# S7CAS-PLEIADES-CARTE-MERE_P01_MOTORS.net
KiCad netlist of a schematic drawn in Altium Designer
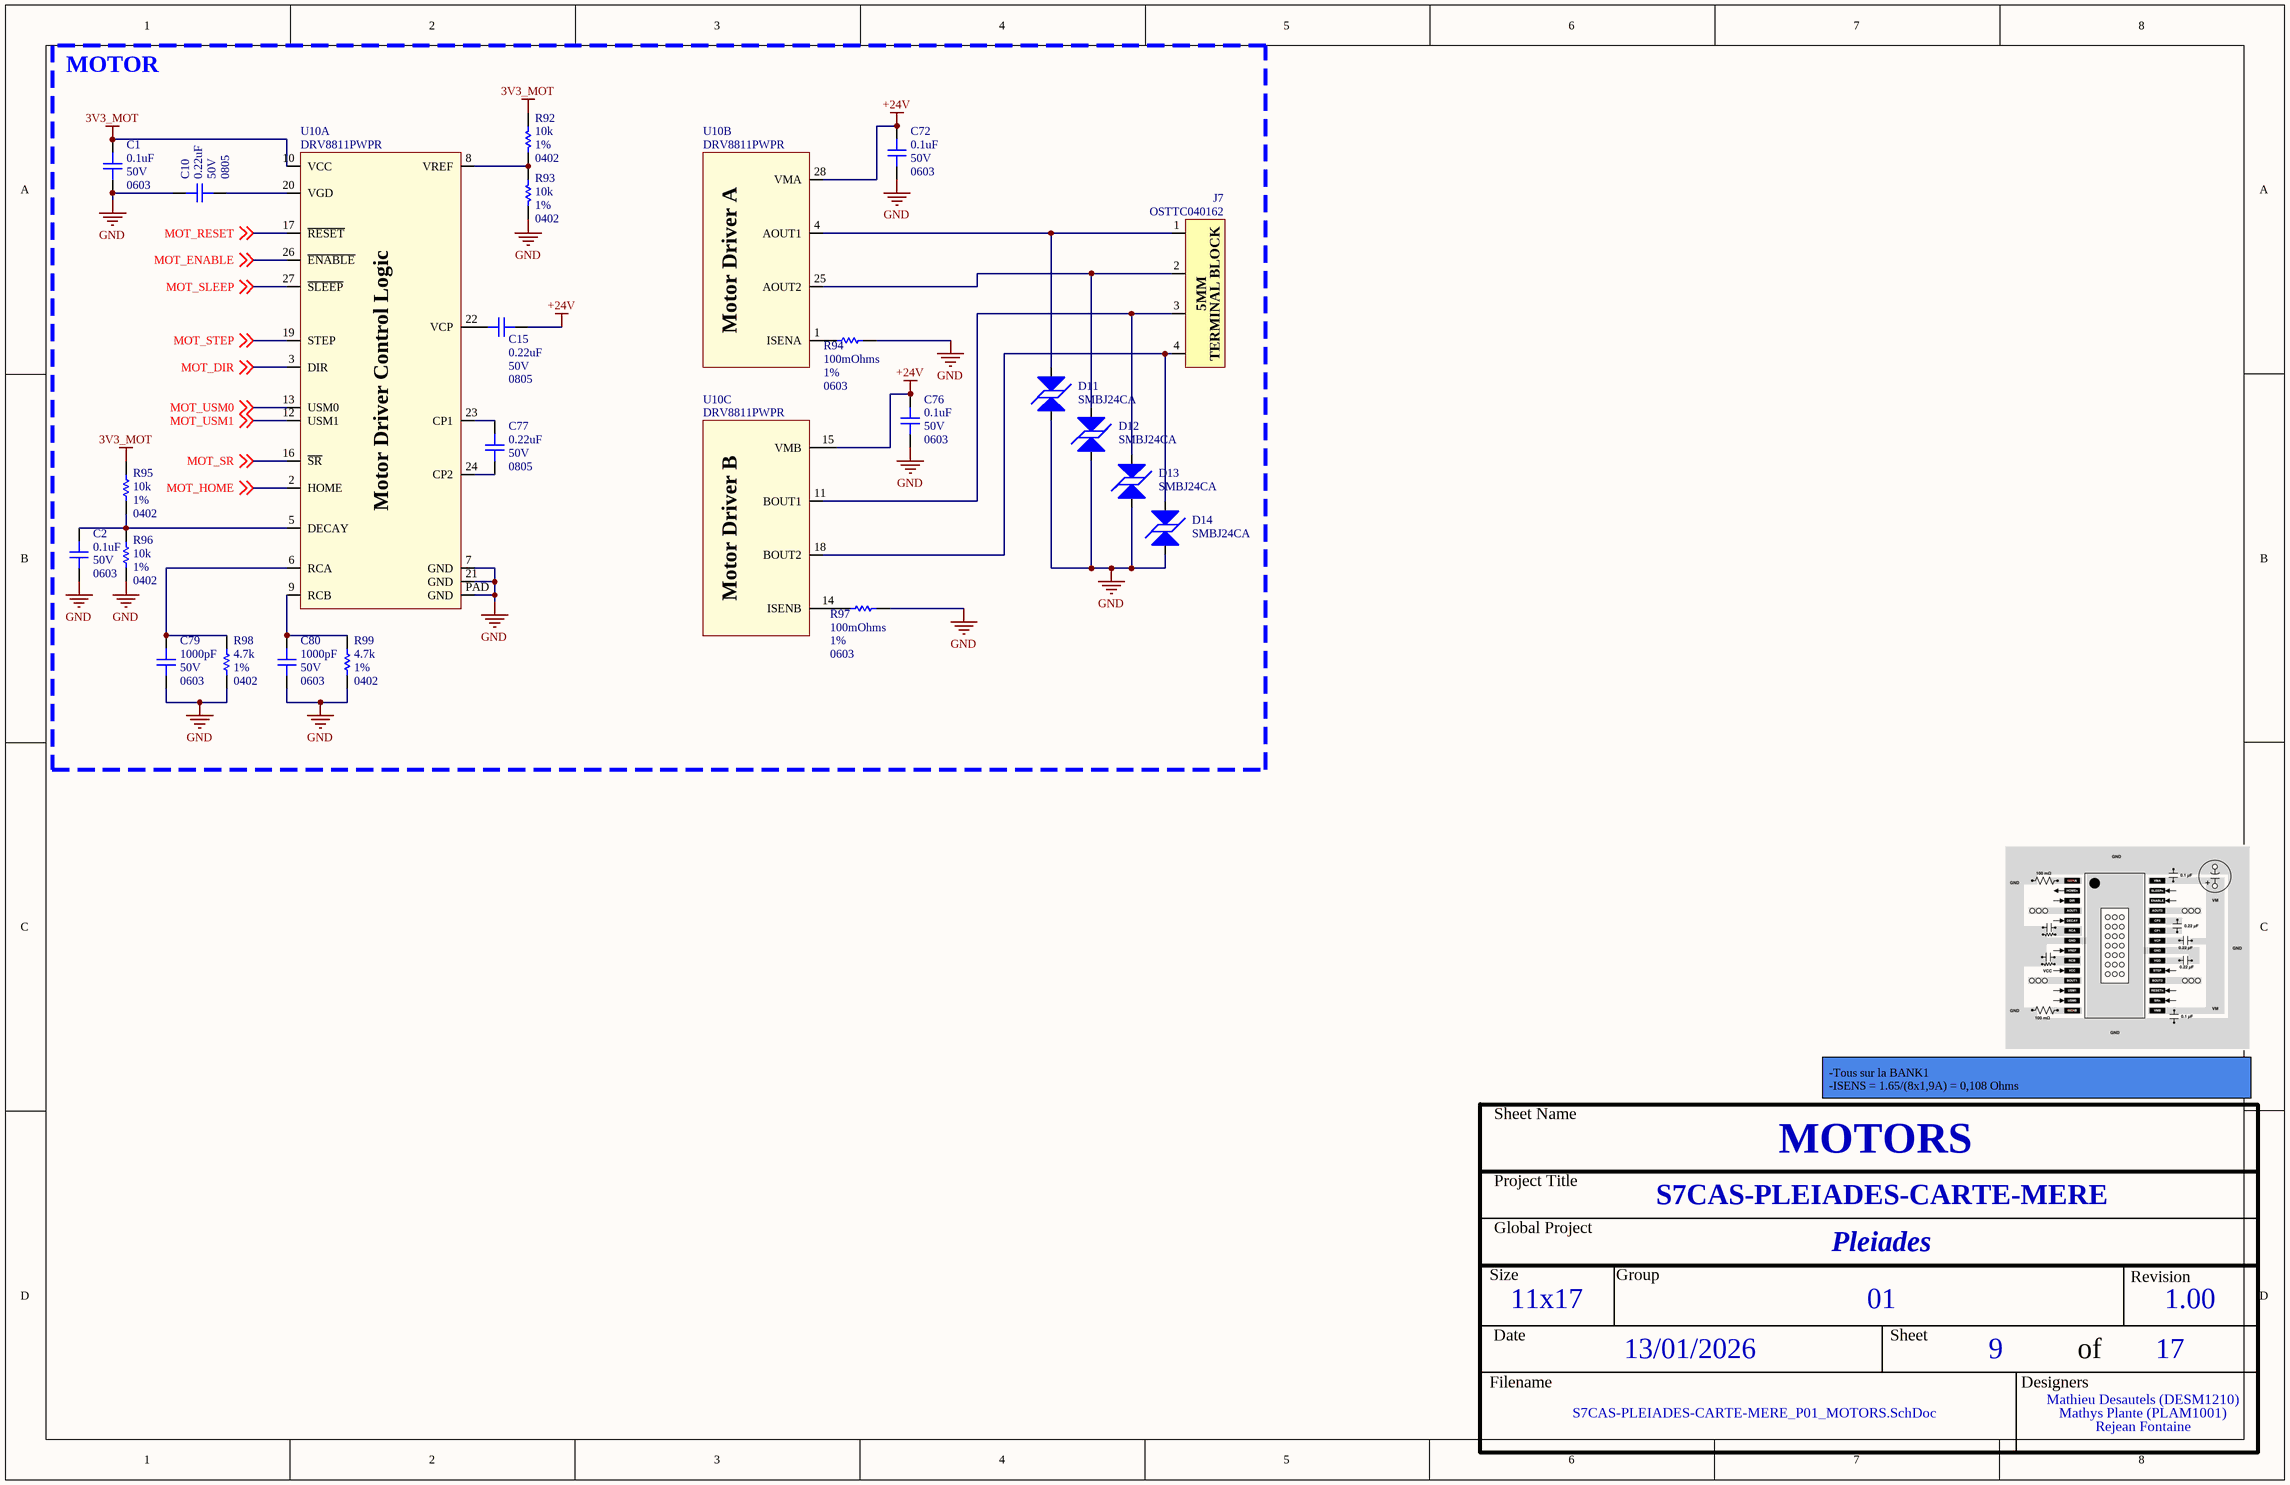
[diagram p0: S7CAS-PLEIADES-CARTE-MERE_P01_MOTORS.SchDoc]

(export (version "E")
  (design (tool "Eeschema 10.0.6"))
  (components
    (comp (ref "C1")
      (value "0.1uF")
      (footprint "CAP_0603")
      (description "0.1 µF ±10% 50V Ceramic Capacitor X7R 0603 (1608 Metric)")
      (fields
        (field (name "MFG") "KEMET")
        (field (name "MFG PART NUMBER") "C0603C104K5RACTU")
        (field (name "VOLTAGE") "50V")
        (field (name "PACKAGE") "0603")
        (field (name "CREATEDBY") "Jonathan Bouchard")
      )
      (libsource (lib "s7cas_lib2023") (part "CAP - 0603"))
    )
    (comp (ref "C2")
      (value "0.1uF")
      (footprint "CAP_0603")
      (description "0.1 µF ±10% 50V Ceramic Capacitor X7R 0603 (1608 Metric)")
      (fields
        (field (name "MFG") "KEMET")
        (field (name "MFG PART NUMBER") "C0603C104K5RACTU")
        (field (name "VOLTAGE") "50V")
        (field (name "PACKAGE") "0603")
        (field (name "CREATEDBY") "Jonathan Bouchard")
      )
      (libsource (lib "s7cas_lib2023") (part "CAP - 0603"))
    )
    (comp (ref "C10")
      (value "0.22uF")
      (footprint "CAP_0805")
      (description "0.22 µF ±10% 50V Ceramic Capacitor X7R 0805 (2012 Metric)")
      (fields
        (field (name "MFG PART NUMBER") "C0805C224K5RACTU")
        (field (name "VOLTAGE") "50V")
        (field (name "PACKAGE") "0805")
        (field (name "Comment") "CAP - 0805")
        (field (name "CREATEDBY") "Jonathan Bouchard")
      )
      (libsource (lib "s7cas_lib2023") (part "CAP - 0805"))
    )
    (comp (ref "C15")
      (value "0.22uF")
      (footprint "CAP_0805")
      (description "0.22 µF ±10% 50V Ceramic Capacitor X7R 0805 (2012 Metric)")
      (fields
        (field (name "MFG PART NUMBER") "C0805C224K5RACTU")
        (field (name "VOLTAGE") "50V")
        (field (name "PACKAGE") "0805")
        (field (name "Comment") "CAP - 0805")
        (field (name "CREATEDBY") "Jonathan Bouchard")
      )
      (libsource (lib "s7cas_lib2023") (part "CAP - 0805"))
    )
    (comp (ref "C72")
      (value "0.1uF")
      (footprint "CAP_0603")
      (description "0.1 µF ±10% 50V Ceramic Capacitor X7R 0603 (1608 Metric)")
      (fields
        (field (name "MFG") "KEMET")
        (field (name "MFG PART NUMBER") "C0603C104K5RACTU")
        (field (name "VOLTAGE") "50V")
        (field (name "PACKAGE") "0603")
        (field (name "CREATEDBY") "Jonathan Bouchard")
      )
      (libsource (lib "s7cas_lib2023") (part "CAP - 0603"))
    )
    (comp (ref "C76")
      (value "0.1uF")
      (footprint "CAP_0603")
      (description "0.1 µF ±10% 50V Ceramic Capacitor X7R 0603 (1608 Metric)")
      (fields
        (field (name "MFG") "KEMET")
        (field (name "MFG PART NUMBER") "C0603C104K5RACTU")
        (field (name "VOLTAGE") "50V")
        (field (name "PACKAGE") "0603")
        (field (name "CREATEDBY") "Jonathan Bouchard")
      )
      (libsource (lib "s7cas_lib2023") (part "CAP - 0603"))
    )
    (comp (ref "C77")
      (value "0.22uF")
      (footprint "CAP_0805")
      (description "0.22 µF ±10% 50V Ceramic Capacitor X7R 0805 (2012 Metric)")
      (fields
        (field (name "MFG PART NUMBER") "C0805C224K5RACTU")
        (field (name "VOLTAGE") "50V")
        (field (name "PACKAGE") "0805")
        (field (name "Comment") "CAP - 0805")
        (field (name "CREATEDBY") "Jonathan Bouchard")
      )
      (libsource (lib "s7cas_lib2023") (part "CAP - 0805"))
    )
    (comp (ref "C79")
      (value "1000pF")
      (footprint "CAP_0603")
      (description "1000 pF ±10% 50V Ceramic Capacitor X7R 0603 (1608 Metric)")
      (fields
        (field (name "MFG") "KEMET")
        (field (name "MFG PART NUMBER") "C0603C102K5RACTU")
        (field (name "VOLTAGE") "50V")
        (field (name "PACKAGE") "0603")
        (field (name "CREATEDBY") "Jonathan Bouchard")
      )
      (libsource (lib "s7cas_lib2023") (part "CAP - 0603"))
    )
    (comp (ref "C80")
      (value "1000pF")
      (footprint "CAP_0603")
      (description "1000 pF ±10% 50V Ceramic Capacitor X7R 0603 (1608 Metric)")
      (fields
        (field (name "MFG") "KEMET")
        (field (name "MFG PART NUMBER") "C0603C102K5RACTU")
        (field (name "VOLTAGE") "50V")
        (field (name "PACKAGE") "0603")
        (field (name "CREATEDBY") "Jonathan Bouchard")
      )
      (libsource (lib "s7cas_lib2023") (part "CAP - 0603"))
    )
    (comp (ref "D11")
      (value "SMBJ24CA")
      (footprint "TVS_PWR_SMBJ36CA")
      (description "TVS - 24V 26.7V 600W - DO214AA")
      (fields
        (field (name "CREATEDBY/DATE") "Arnaud Samson - 06/07/18")
        (field (name "VERIFIEDBY") "Jonathan Bouchard - 2018-07-13")
      )
      (libsource (lib "s7cas_lib2023") (part "TVS_PWR_SMBJ24CA"))
    )
    (comp (ref "D12")
      (value "SMBJ24CA")
      (footprint "TVS_PWR_SMBJ36CA")
      (description "TVS - 24V 26.7V 600W - DO214AA")
      (fields
        (field (name "CREATEDBY/DATE") "Arnaud Samson - 06/07/18")
        (field (name "VERIFIEDBY") "Jonathan Bouchard - 2018-07-13")
      )
      (libsource (lib "s7cas_lib2023") (part "TVS_PWR_SMBJ24CA"))
    )
    (comp (ref "D13")
      (value "SMBJ24CA")
      (footprint "TVS_PWR_SMBJ36CA")
      (description "TVS - 24V 26.7V 600W - DO214AA")
      (fields
        (field (name "CREATEDBY/DATE") "Arnaud Samson - 06/07/18")
        (field (name "VERIFIEDBY") "Jonathan Bouchard - 2018-07-13")
      )
      (libsource (lib "s7cas_lib2023") (part "TVS_PWR_SMBJ24CA"))
    )
    (comp (ref "D14")
      (value "SMBJ24CA")
      (footprint "TVS_PWR_SMBJ36CA")
      (description "TVS - 24V 26.7V 600W - DO214AA")
      (fields
        (field (name "CREATEDBY/DATE") "Arnaud Samson - 06/07/18")
        (field (name "VERIFIEDBY") "Jonathan Bouchard - 2018-07-13")
      )
      (libsource (lib "s7cas_lib2023") (part "TVS_PWR_SMBJ24CA"))
    )
    (comp (ref "J7")
      (value "OSTTC040162")
      (footprint "CONN_TERMINAL_OSTTA040161")
      (description "CONN -  TERMINAL BLOCK 4POS 5MM - TH")
      (fields (field (name "MFG") "On Shore Technology Inc.") (field (name "CREATEDBY") "Jonathan Bouchard"))
      (libsource (lib "s7cas_lib2023") (part "CONN_TERMINAL_OSTTC040162"))
    )
    (comp (ref "R92")
      (value "10k")
      (footprint "RES_0402")
      (description "10 kOhms ±1% 0.063W, 1/16W Chip Resistor 0402 (1005 Metric) Automotive AEC-Q200 Thick Film")
      (fields
        (field (name "VOLTAGE") "75V")
        (field (name "MFG PART NUMBER") "RMCF0402FT10K0")
        (field (name "PACKAGE") "0402")
        (field (name "PRECISION") "1%")
        (field (name "CREATEDBY") "Jonathan Bouchard")
      )
      (libsource (lib "s7cas_lib2023") (part "RES - 0402"))
    )
    (comp (ref "R93")
      (value "10k")
      (footprint "RES_0402")
      (description "10 kOhms ±1% 0.063W, 1/16W Chip Resistor 0402 (1005 Metric) Automotive AEC-Q200 Thick Film")
      (fields
        (field (name "VOLTAGE") "75V")
        (field (name "MFG PART NUMBER") "RMCF0402FT10K0")
        (field (name "PACKAGE") "0402")
        (field (name "PRECISION") "1%")
        (field (name "CREATEDBY") "Jonathan Bouchard")
      )
      (libsource (lib "s7cas_lib2023") (part "RES - 0402"))
    )
    (comp (ref "R94")
      (value "100mOhms")
      (footprint "RES_0603")
      (fields
        (field (name "MFG") "Panasonic Electronic Components")
        (field (name "MFG PART NUMBER") "ERJ-3BWFR100V")
        (field (name "PACKAGE") "0603")
        (field (name "PRECISION") "1%")
        (field (name "Comment") "RES - 0603")
        (field (name "CREATEDBY") "Jonathan Bouchard")
      )
      (libsource (lib "s7cas_lib2023") (part "RES - 0603"))
    )
    (comp (ref "R95")
      (value "10k")
      (footprint "RES_0402")
      (description "10 kOhms ±1% 0.063W, 1/16W Chip Resistor 0402 (1005 Metric) Automotive AEC-Q200 Thick Film")
      (fields
        (field (name "VOLTAGE") "75V")
        (field (name "MFG PART NUMBER") "RMCF0402FT10K0")
        (field (name "PACKAGE") "0402")
        (field (name "PRECISION") "1%")
        (field (name "CREATEDBY") "Jonathan Bouchard")
      )
      (libsource (lib "s7cas_lib2023") (part "RES - 0402"))
    )
    (comp (ref "R96")
      (value "10k")
      (footprint "RES_0402")
      (description "10 kOhms ±1% 0.063W, 1/16W Chip Resistor 0402 (1005 Metric) Automotive AEC-Q200 Thick Film")
      (fields
        (field (name "VOLTAGE") "75V")
        (field (name "MFG PART NUMBER") "RMCF0402FT10K0")
        (field (name "PACKAGE") "0402")
        (field (name "PRECISION") "1%")
        (field (name "CREATEDBY") "Jonathan Bouchard")
      )
      (libsource (lib "s7cas_lib2023") (part "RES - 0402"))
    )
    (comp (ref "R97")
      (value "100mOhms")
      (footprint "RES_0603")
      (fields
        (field (name "MFG") "Panasonic Electronic Components")
        (field (name "MFG PART NUMBER") "ERJ-3BWFR100V")
        (field (name "PACKAGE") "0603")
        (field (name "PRECISION") "1%")
        (field (name "Comment") "RES - 0603")
        (field (name "CREATEDBY") "Jonathan Bouchard")
      )
      (libsource (lib "s7cas_lib2023") (part "RES - 0603"))
    )
    (comp (ref "R98")
      (value "4.7k")
      (footprint "RES_0402")
      (description "4.7 kOhms ±1% 0.063W, 1/16W Chip Resistor 0402 (1005 Metric) Moisture Resistant Thick Film")
      (fields
        (field (name "VOLTAGE") "75V")
        (field (name "MFG PART NUMBER") "RC0402FR-074K7L")
        (field (name "PACKAGE") "0402")
        (field (name "PRECISION") "1%")
        (field (name "CREATEDBY") "Jonathan Bouchard")
      )
      (libsource (lib "s7cas_lib2023") (part "RES - 0402"))
    )
    (comp (ref "R99")
      (value "4.7k")
      (footprint "RES_0402")
      (description "4.7 kOhms ±1% 0.063W, 1/16W Chip Resistor 0402 (1005 Metric) Moisture Resistant Thick Film")
      (fields
        (field (name "VOLTAGE") "75V")
        (field (name "MFG PART NUMBER") "RC0402FR-074K7L")
        (field (name "PACKAGE") "0402")
        (field (name "PRECISION") "1%")
        (field (name "CREATEDBY") "Jonathan Bouchard")
      )
      (libsource (lib "s7cas_lib2023") (part "RES - 0402"))
    )
    (comp (ref "U10")
      (value "DRV8811PWPR")
      (footprint "POW_MOTOR_DRV8811PWPR")
      (description "POW - STEPPER MOTOR DRIVER - SOP-28")
      (fields
        (field (name "VOLTAGE") "3 V ~ 5.5 V / 8 V ~ 38 V")
        (field (name "MFG") "Texas Instrument")
        (field (name "CREATEDBY") "Jonathan Bouchard")
      )
      (libsource (lib "s7cas_lib2023") (part "POW_MOTOR_DRV8811PWPR"))
    )
  )
  (nets
    (net (code "1") (name "+24V") (class "Default")
      (node (ref "C15") (pin "1") (pinfunction "1_1") (pintype "passive"))
      (node (ref "C72") (pin "2") (pinfunction "2_2") (pintype "passive"))
      (node (ref "C76") (pin "2") (pinfunction "2_2") (pintype "passive"))
      (node (ref "U10") (pin "15") (pinfunction "VMB_15") (pintype "passive"))
      (node (ref "U10") (pin "28") (pinfunction "VMA_28") (pintype "passive"))
    )
    (net (code "2") (name "3V3_MOT") (class "Default")
      (node (ref "C1") (pin "2") (pinfunction "2_2") (pintype "passive"))
      (node (ref "R92") (pin "2") (pinfunction "2_2") (pintype "passive"))
      (node (ref "R95") (pin "2") (pinfunction "2_2") (pintype "passive"))
      (node (ref "U10") (pin "10") (pinfunction "VCC_10") (pintype "passive"))
    )
    (net (code "3") (name "GND") (class "Default")
      (node (ref "C1") (pin "1") (pinfunction "1_1") (pintype "passive"))
      (node (ref "C10") (pin "2") (pinfunction "2_2") (pintype "passive"))
      (node (ref "C2") (pin "1") (pinfunction "1_1") (pintype "passive"))
      (node (ref "C72") (pin "1") (pinfunction "1_1") (pintype "passive"))
      (node (ref "C76") (pin "1") (pinfunction "1_1") (pintype "passive"))
      (node (ref "C79") (pin "1") (pinfunction "1_1") (pintype "passive"))
      (node (ref "C80") (pin "1") (pinfunction "1_1") (pintype "passive"))
      (node (ref "D11") (pin "2") (pinfunction "2_2") (pintype "passive"))
      (node (ref "D12") (pin "2") (pinfunction "2_2") (pintype "passive"))
      (node (ref "D13") (pin "2") (pinfunction "2_2") (pintype "passive"))
      (node (ref "D14") (pin "2") (pinfunction "2_2") (pintype "passive"))
      (node (ref "R93") (pin "1") (pinfunction "1_1") (pintype "passive"))
      (node (ref "R94") (pin "1") (pinfunction "1_1") (pintype "passive"))
      (node (ref "R96") (pin "1") (pinfunction "1_1") (pintype "passive"))
      (node (ref "R97") (pin "1") (pinfunction "1_1") (pintype "passive"))
      (node (ref "R98") (pin "1") (pinfunction "1_1") (pintype "passive"))
      (node (ref "R99") (pin "1") (pinfunction "1_1") (pintype "passive"))
      (node (ref "U10") (pin "21") (pinfunction "GND_21") (pintype "passive"))
      (node (ref "U10") (pin "7") (pinfunction "GND_7") (pintype "passive"))
      (node (ref "U10") (pin "PAD") (pinfunction "GND_PAD") (pintype "passive"))
    )
    (net (code "4") (name "MOT_DIR") (class "Default")
      (node (ref "U10") (pin "3") (pinfunction "DIR_3") (pintype "passive"))
    )
    (net (code "5") (name "MOT_ENABLE") (class "Default")
      (node (ref "U10") (pin "26") (pinfunction "~{ENABLE}_26") (pintype "passive"))
    )
    (net (code "6") (name "MOT_HOME") (class "Default")
      (node (ref "U10") (pin "2") (pinfunction "HOME_2") (pintype "passive"))
    )
    (net (code "7") (name "MOT_RESET") (class "Default")
      (node (ref "U10") (pin "17") (pinfunction "~{RESET}_17") (pintype "passive"))
    )
    (net (code "8") (name "MOT_SLEEP") (class "Default")
      (node (ref "U10") (pin "27") (pinfunction "~{SLEEP}_27") (pintype "passive"))
    )
    (net (code "9") (name "MOT_SR") (class "Default")
      (node (ref "U10") (pin "16") (pinfunction "~{SR}_16") (pintype "passive"))
    )
    (net (code "10") (name "MOT_STEP") (class "Default")
      (node (ref "U10") (pin "19") (pinfunction "STEP_19") (pintype "passive"))
    )
    (net (code "11") (name "MOT_USM0") (class "Default")
      (node (ref "U10") (pin "13") (pinfunction "USM0_13") (pintype "passive"))
    )
    (net (code "12") (name "MOT_USM1") (class "Default")
      (node (ref "U10") (pin "12") (pinfunction "USM1_12") (pintype "passive"))
    )
    (net (code "13") (name "Net-(U10A-CP1)") (class "Default")
      (node (ref "C77") (pin "2") (pinfunction "2_2") (pintype "passive"))
      (node (ref "U10") (pin "23") (pinfunction "CP1_23") (pintype "passive"))
    )
    (net (code "14") (name "Net-(U10A-CP2)") (class "Default")
      (node (ref "C77") (pin "1") (pinfunction "1_1") (pintype "passive"))
      (node (ref "U10") (pin "24") (pinfunction "CP2_24") (pintype "passive"))
    )
    (net (code "15") (name "Net-(U10A-DECAY)") (class "Default")
      (node (ref "C2") (pin "2") (pinfunction "2_2") (pintype "passive"))
      (node (ref "R95") (pin "1") (pinfunction "1_1") (pintype "passive"))
      (node (ref "R96") (pin "2") (pinfunction "2_2") (pintype "passive"))
      (node (ref "U10") (pin "5") (pinfunction "DECAY_5") (pintype "passive"))
    )
    (net (code "16") (name "Net-(U10A-RCA)") (class "Default")
      (node (ref "C79") (pin "2") (pinfunction "2_2") (pintype "passive"))
      (node (ref "R98") (pin "2") (pinfunction "2_2") (pintype "passive"))
      (node (ref "U10") (pin "6") (pinfunction "RCA_6") (pintype "passive"))
    )
    (net (code "17") (name "Net-(U10A-RCB)") (class "Default")
      (node (ref "C80") (pin "2") (pinfunction "2_2") (pintype "passive"))
      (node (ref "R99") (pin "2") (pinfunction "2_2") (pintype "passive"))
      (node (ref "U10") (pin "9") (pinfunction "RCB_9") (pintype "passive"))
    )
    (net (code "18") (name "Net-(U10A-VCP)") (class "Default")
      (node (ref "C15") (pin "2") (pinfunction "2_2") (pintype "passive"))
      (node (ref "U10") (pin "22") (pinfunction "VCP_22") (pintype "passive"))
    )
    (net (code "19") (name "Net-(U10A-VGD)") (class "Default")
      (node (ref "C10") (pin "1") (pinfunction "1_1") (pintype "passive"))
      (node (ref "U10") (pin "20") (pinfunction "VGD_20") (pintype "passive"))
    )
    (net (code "20") (name "Net-(U10A-VREF)") (class "Default")
      (node (ref "R92") (pin "1") (pinfunction "1_1") (pintype "passive"))
      (node (ref "R93") (pin "2") (pinfunction "2_2") (pintype "passive"))
      (node (ref "U10") (pin "8") (pinfunction "VREF_8") (pintype "passive"))
    )
    (net (code "21") (name "Net-(U10B-AOUT1)") (class "Default")
      (node (ref "D11") (pin "1") (pinfunction "1_1") (pintype "passive"))
      (node (ref "J7") (pin "1") (pinfunction "1_1") (pintype "passive"))
      (node (ref "U10") (pin "4") (pinfunction "AOUT1_4") (pintype "passive"))
    )
    (net (code "22") (name "Net-(U10B-AOUT2)") (class "Default")
      (node (ref "D12") (pin "1") (pinfunction "1_1") (pintype "passive"))
      (node (ref "J7") (pin "2") (pinfunction "2_2") (pintype "passive"))
      (node (ref "U10") (pin "25") (pinfunction "AOUT2_25") (pintype "passive"))
    )
    (net (code "23") (name "Net-(U10B-ISENA)") (class "Default")
      (node (ref "R94") (pin "2") (pinfunction "2_2") (pintype "passive"))
      (node (ref "U10") (pin "1") (pinfunction "ISENA_1") (pintype "passive"))
    )
    (net (code "24") (name "Net-(U10C-BOUT1)") (class "Default")
      (node (ref "D13") (pin "1") (pinfunction "1_1") (pintype "passive"))
      (node (ref "J7") (pin "3") (pinfunction "3_3") (pintype "passive"))
      (node (ref "U10") (pin "11") (pinfunction "BOUT1_11") (pintype "passive"))
    )
    (net (code "25") (name "Net-(U10C-BOUT2)") (class "Default")
      (node (ref "D14") (pin "1") (pinfunction "1_1") (pintype "passive"))
      (node (ref "J7") (pin "4") (pinfunction "4_4") (pintype "passive"))
      (node (ref "U10") (pin "18") (pinfunction "BOUT2_18") (pintype "passive"))
    )
    (net (code "26") (name "Net-(U10C-ISENB)") (class "Default")
      (node (ref "R97") (pin "2") (pinfunction "2_2") (pintype "passive"))
      (node (ref "U10") (pin "14") (pinfunction "ISENB_14") (pintype "passive"))
    )
  )
)
